# Car.net
KiCad netlist of a schematic drawn in EAGLE
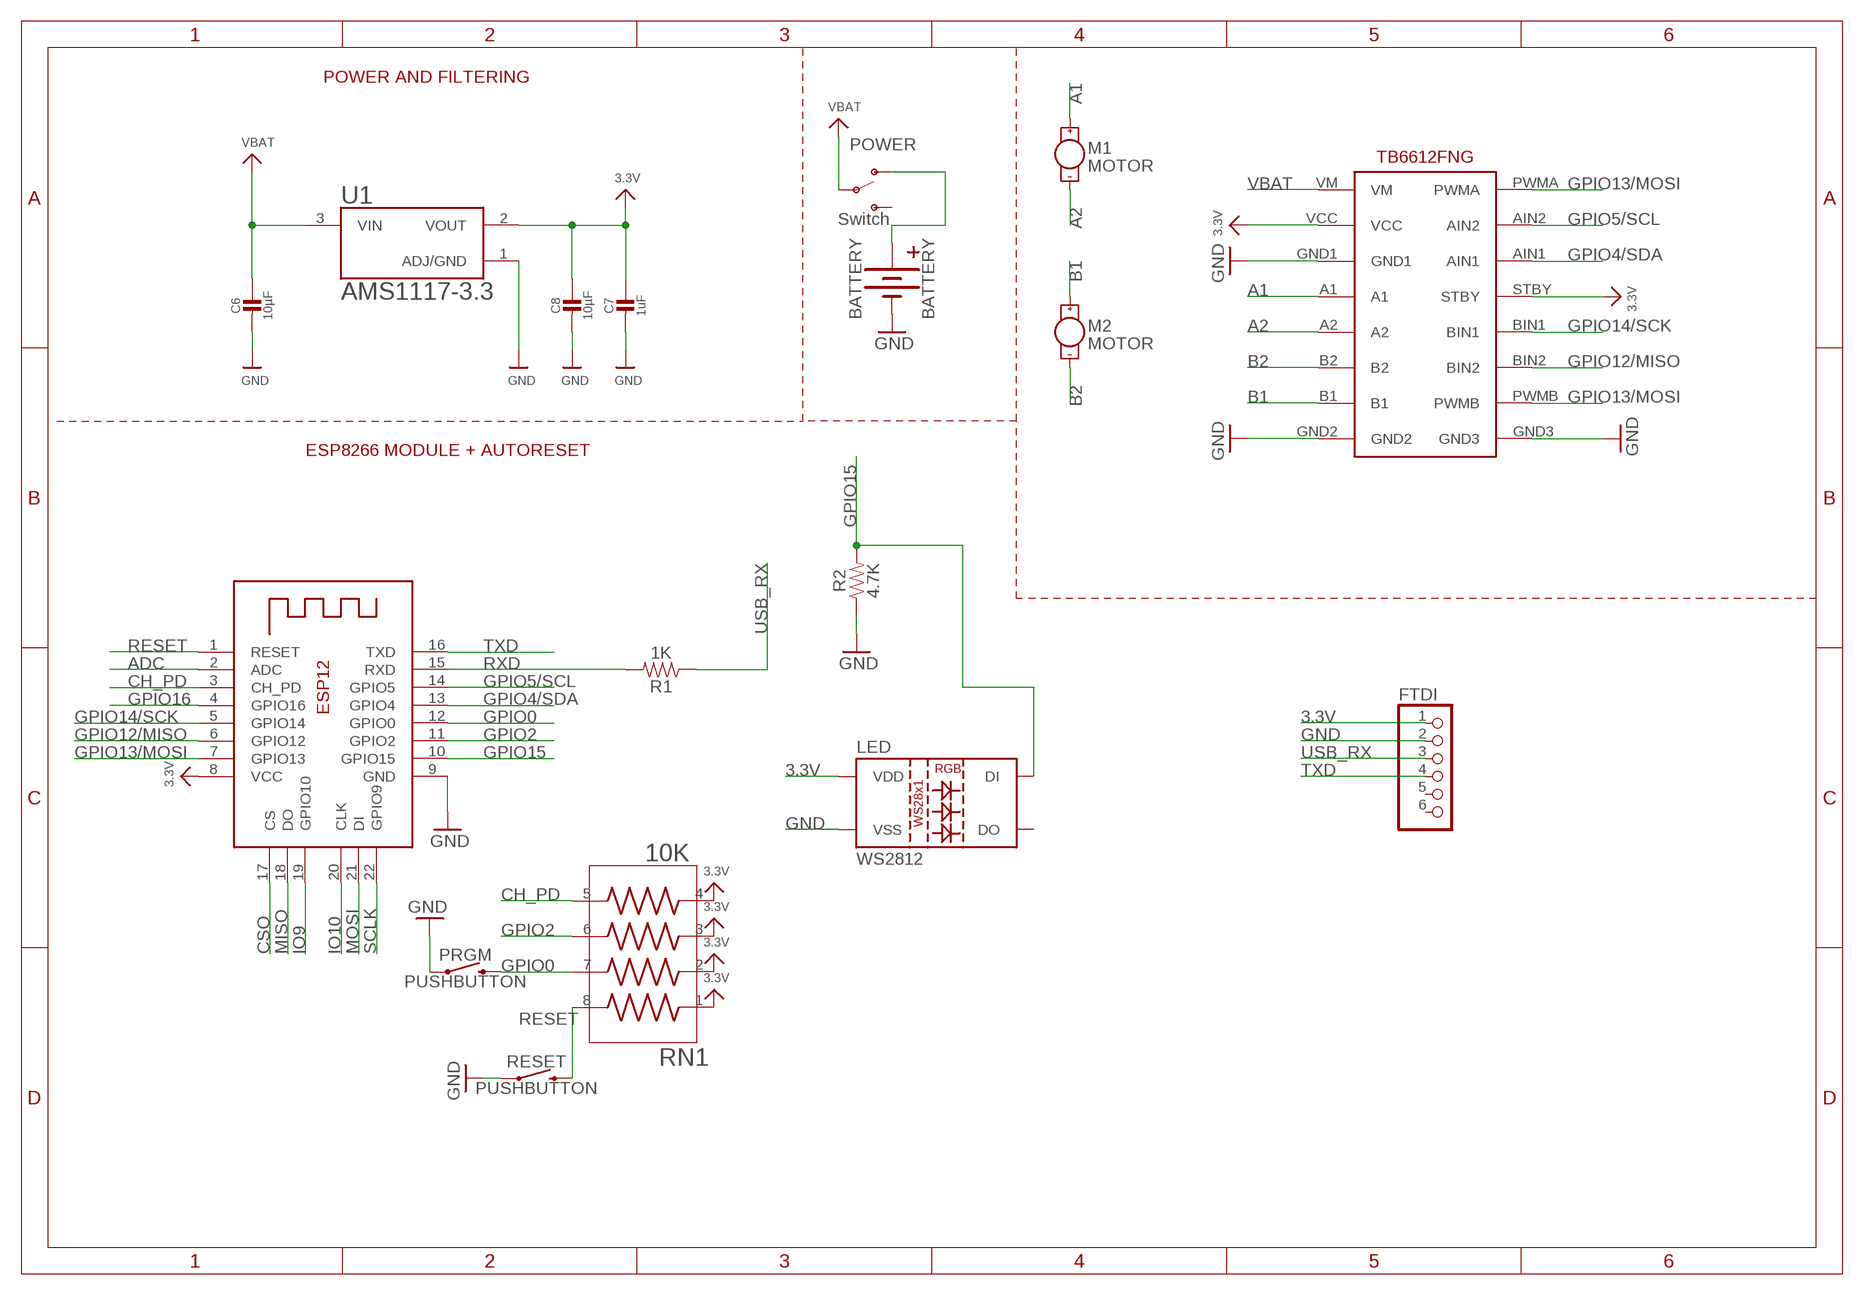
[diagram p0: schematic, sheet 1]

(export (version "E")
  (design (tool "Eeschema 10.0.6"))
  (components
    (comp (ref "BATTERY")
      (value "BATTERY")
      (footprint "eagle-import:BATTERY-AA-KIT")
      (libsource (lib "eagle-import") (part "BATTERY"))
    )
    (comp (ref "C6")
      (value "10µF")
      (footprint "eagle-import:MICROBUILDER__0805")
      (libsource (lib "eagle-import") (part "MICROBUILDER_CAP_CERAMIC_0805"))
    )
    (comp (ref "C7")
      (value "1uF")
      (footprint "eagle-import:MICROBUILDER__0603")
      (libsource (lib "eagle-import") (part "MICROBUILDER_CAP_CERAMIC_0603"))
    )
    (comp (ref "C8")
      (value "10µF")
      (footprint "eagle-import:MICROBUILDER__0805")
      (libsource (lib "eagle-import") (part "MICROBUILDER_CAP_CERAMIC_0805"))
    )
    (comp (ref "FTDI")
      (value "PINHD-1X6")
      (footprint "eagle-import:1X06")
      (libsource (lib "eagle-import") (part "PINHD-1X6"))
    )
    (comp (ref "LED")
      (value "WS2812")
      (footprint "eagle-import:LED-TRICOLOR-5050-IC")
      (libsource (lib "eagle-import") (part "WS2812"))
    )
    (comp (ref "M1")
      (value "MOTOR")
      (footprint "eagle-import:1X02_PLUS_MINUS")
      (libsource (lib "eagle-import") (part "MOTOR"))
    )
    (comp (ref "M2")
      (value "MOTOR")
      (footprint "eagle-import:1X02_PLUS_MINUS")
      (libsource (lib "eagle-import") (part "MOTOR"))
    )
    (comp (ref "POWER")
      (value "Switch")
      (footprint "eagle-import:SWITCH_SPDT_PTH_11.6X4.0MM")
      (libsource (lib "eagle-import") (part "SWITCH_SPDT_SLIDE"))
    )
    (comp (ref "PRGM")
      (value "PUSHBUTTON")
      (footprint "eagle-import:TACTILE_SWITCH_SMD_6.0X3.5MM")
      (libsource (lib "eagle-import") (part "PUSHBUTTON"))
    )
    (comp (ref "R1")
      (value "1K")
      (footprint "eagle-import:1206")
      (libsource (lib "eagle-import") (part "RESISTOR1206"))
    )
    (comp (ref "R2")
      (value "4.7K")
      (footprint "eagle-import:1206")
      (libsource (lib "eagle-import") (part "RESISTOR1206"))
    )
    (comp (ref "RESET")
      (value "PUSHBUTTON")
      (footprint "eagle-import:TACTILE_SWITCH_SMD_6.0X3.5MM")
      (libsource (lib "eagle-import") (part "PUSHBUTTON"))
    )
    (comp (ref "RN1")
      (value "10K")
      (footprint "eagle-import:RESCAF80P320X160X60-8N")
      (fields (field (name "MF") "Bourns") (field (name "MP") "CAY16-750J4LF"))
      (libsource (lib "eagle-import") (part "RESISTOR_ARRAY_1206"))
    )
    (comp (ref "TB1")
      (value "TB6612FNG")
      (footprint "eagle-import:TB6612FNG")
      (libsource (lib "eagle-import") (part "TB6612FNG"))
    )
    (comp (ref "U1")
      (value "AMS1117-3.3")
      (footprint "eagle-import:SOT229P700X180-4N")
      (fields (field (name "MF") "Advanced Monolithic Systems"))
      (libsource (lib "eagle-import") (part "AMS1117-3.3"))
    )
    (comp (ref "X2")
      (value "ESP-12")
      (footprint "eagle-import:ESP-12E")
      (libsource (lib "eagle-import") (part "ESP-12E"))
    )
  )
  (nets
    (net (code "1") (name "/A1") (class "Default")
      (node (ref "M1") (pin "+") (pinfunction "+_+") (pintype "bidirectional"))
      (node (ref "TB1") (pin "A1") (pinfunction "A1_A1") (pintype "bidirectional"))
    )
    (net (code "2") (name "/A2") (class "Default")
      (node (ref "M1") (pin "-") (pinfunction "-_-") (pintype "bidirectional"))
      (node (ref "TB1") (pin "A2") (pinfunction "A2_A2") (pintype "bidirectional"))
    )
    (net (code "3") (name "/ADC") (class "Default")
      (node (ref "X2") (pin "2") (pinfunction "ADC_2") (pintype "passive"))
    )
    (net (code "4") (name "/B1") (class "Default")
      (node (ref "M2") (pin "+") (pinfunction "+_+") (pintype "bidirectional"))
      (node (ref "TB1") (pin "B1") (pinfunction "B1_B1") (pintype "bidirectional"))
    )
    (net (code "5") (name "/B2") (class "Default")
      (node (ref "M2") (pin "-") (pinfunction "-_-") (pintype "bidirectional"))
      (node (ref "TB1") (pin "B2") (pinfunction "B2_B2") (pintype "bidirectional"))
    )
    (net (code "6") (name "/CH_PD") (class "Default")
      (node (ref "RN1") (pin "5") (pinfunction "5_5") (pintype "passive"))
      (node (ref "X2") (pin "3") (pinfunction "CH_PD_3") (pintype "input"))
    )
    (net (code "7") (name "/CSO") (class "Default")
      (node (ref "X2") (pin "17") (pinfunction "CS_17") (pintype "bidirectional"))
    )
    (net (code "8") (name "/GPIO0") (class "Default")
      (node (ref "PRGM") (pin "2") (pinfunction "2_2") (pintype "passive"))
      (node (ref "RN1") (pin "7") (pinfunction "7_7") (pintype "passive"))
      (node (ref "X2") (pin "12") (pinfunction "GPIO0_12") (pintype "bidirectional"))
    )
    (net (code "9") (name "/GPIO2") (class "Default")
      (node (ref "RN1") (pin "6") (pinfunction "6_6") (pintype "passive"))
      (node (ref "X2") (pin "11") (pinfunction "GPIO2_11") (pintype "bidirectional"))
    )
    (net (code "10") (name "/GPIO4{slash}SDA") (class "Default")
      (node (ref "TB1") (pin "AIN1") (pinfunction "AIN1_AIN1") (pintype "bidirectional"))
      (node (ref "X2") (pin "13") (pinfunction "GPIO4_13") (pintype "bidirectional"))
    )
    (net (code "11") (name "/GPIO5{slash}SCL") (class "Default")
      (node (ref "TB1") (pin "AIN2") (pinfunction "AIN2_AIN2") (pintype "bidirectional"))
      (node (ref "X2") (pin "14") (pinfunction "GPIO5_14") (pintype "bidirectional"))
    )
    (net (code "12") (name "/GPIO12{slash}MISO") (class "Default")
      (node (ref "TB1") (pin "BIN2") (pinfunction "BIN2_BIN2") (pintype "bidirectional"))
      (node (ref "X2") (pin "6") (pinfunction "GPIO12_6") (pintype "bidirectional"))
    )
    (net (code "13") (name "/GPIO13{slash}MOSI") (class "Default")
      (node (ref "TB1") (pin "PWMA") (pinfunction "PWMA_PWMA") (pintype "bidirectional"))
      (node (ref "TB1") (pin "PWMB") (pinfunction "PWMB_PWMB") (pintype "bidirectional"))
      (node (ref "X2") (pin "7") (pinfunction "GPIO13_7") (pintype "bidirectional"))
    )
    (net (code "14") (name "/GPIO14{slash}SCK") (class "Default")
      (node (ref "TB1") (pin "BIN1") (pinfunction "BIN1_BIN1") (pintype "bidirectional"))
      (node (ref "X2") (pin "5") (pinfunction "GPIO14_5") (pintype "bidirectional"))
    )
    (net (code "15") (name "/GPIO15") (class "Default")
      (node (ref "LED") (pin "DIN") (pinfunction "DI_DIN") (pintype "bidirectional"))
      (node (ref "R2") (pin "2") (pinfunction "2_2") (pintype "passive"))
      (node (ref "X2") (pin "10") (pinfunction "GPIO15_10") (pintype "bidirectional"))
    )
    (net (code "16") (name "/GPIO16") (class "Default")
      (node (ref "X2") (pin "4") (pinfunction "GPIO16_4") (pintype "bidirectional"))
    )
    (net (code "17") (name "/IO9") (class "Default")
      (node (ref "X2") (pin "19") (pinfunction "GPIO10_19") (pintype "bidirectional"))
    )
    (net (code "18") (name "/IO10") (class "Default")
      (node (ref "X2") (pin "20") (pinfunction "CLK_20") (pintype "bidirectional"))
    )
    (net (code "19") (name "/MISO") (class "Default")
      (node (ref "X2") (pin "18") (pinfunction "DO_18") (pintype "bidirectional"))
    )
    (net (code "20") (name "/MOSI") (class "Default")
      (node (ref "X2") (pin "21") (pinfunction "DI_21") (pintype "bidirectional"))
    )
    (net (code "21") (name "/RESET") (class "Default")
      (node (ref "RESET") (pin "2") (pinfunction "2_2") (pintype "passive"))
      (node (ref "RN1") (pin "8") (pinfunction "8_8") (pintype "passive"))
      (node (ref "X2") (pin "1") (pinfunction "RESET_1") (pintype "input"))
    )
    (net (code "22") (name "/RXD") (class "Default")
      (node (ref "R1") (pin "2") (pinfunction "2_2") (pintype "passive"))
      (node (ref "X2") (pin "15") (pinfunction "RXD_15") (pintype "input"))
    )
    (net (code "23") (name "/SCLK") (class "Default")
      (node (ref "X2") (pin "22") (pinfunction "GPIO9_22") (pintype "bidirectional"))
    )
    (net (code "24") (name "/TXD") (class "Default")
      (node (ref "FTDI") (pin "4") (pinfunction "4_4") (pintype "passive"))
      (node (ref "X2") (pin "16") (pinfunction "TXD_16") (pintype "output"))
    )
    (net (code "25") (name "/USB_RX") (class "Default")
      (node (ref "FTDI") (pin "3") (pinfunction "3_3") (pintype "passive"))
      (node (ref "R1") (pin "1") (pinfunction "1_1") (pintype "passive"))
    )
    (net (code "26") (name "3.3V") (class "Default")
      (node (ref "C7") (pin "1") (pinfunction "1_1") (pintype "passive"))
      (node (ref "C8") (pin "1") (pinfunction "1_1") (pintype "passive"))
      (node (ref "FTDI") (pin "1") (pinfunction "1_1") (pintype "passive"))
      (node (ref "LED") (pin "VDD") (pinfunction "VDD_VDD") (pintype "bidirectional"))
      (node (ref "RN1") (pin "1") (pinfunction "1_1") (pintype "passive"))
      (node (ref "RN1") (pin "2") (pinfunction "2_2") (pintype "passive"))
      (node (ref "RN1") (pin "3") (pinfunction "3_3") (pintype "passive"))
      (node (ref "RN1") (pin "4") (pinfunction "4_4") (pintype "passive"))
      (node (ref "TB1") (pin "STBY") (pinfunction "STBY_STBY") (pintype "bidirectional"))
      (node (ref "TB1") (pin "VCC") (pinfunction "VCC_VCC") (pintype "bidirectional"))
      (node (ref "U1") (pin "2") (pinfunction "VOUT_2") (pintype "output"))
      (node (ref "X2") (pin "8") (pinfunction "VCC_8") (pintype "power_in"))
    )
    (net (code "27") (name "GND") (class "Default")
      (node (ref "BATTERY") (pin "GND") (pinfunction "-_GND") (pintype "power_in"))
      (node (ref "C6") (pin "2") (pinfunction "2_2") (pintype "passive"))
      (node (ref "C7") (pin "2") (pinfunction "2_2") (pintype "passive"))
      (node (ref "C8") (pin "2") (pinfunction "2_2") (pintype "passive"))
      (node (ref "FTDI") (pin "2") (pinfunction "2_2") (pintype "passive"))
      (node (ref "LED") (pin "VSS") (pinfunction "VSS_VSS") (pintype "bidirectional"))
      (node (ref "PRGM") (pin "1") (pinfunction "1_1") (pintype "passive"))
      (node (ref "R2") (pin "1") (pinfunction "1_1") (pintype "passive"))
      (node (ref "RESET") (pin "1") (pinfunction "1_1") (pintype "passive"))
      (node (ref "TB1") (pin "GND1") (pinfunction "GND1_GND1") (pintype "bidirectional"))
      (node (ref "TB1") (pin "GND2") (pinfunction "GND2_GND2") (pintype "bidirectional"))
      (node (ref "TB1") (pin "GND3") (pinfunction "GND3_GND3") (pintype "bidirectional"))
      (node (ref "U1") (pin "1") (pinfunction "ADJ/GND_1") (pintype "power_in"))
      (node (ref "X2") (pin "9") (pinfunction "GND_9") (pintype "power_in"))
    )
    (net (code "28") (name "Net-(BATTERY-+)") (class "Default")
      (node (ref "BATTERY") (pin "PWR") (pinfunction "+_PWR") (pintype "power_in"))
      (node (ref "POWER") (pin "1") (pinfunction "O_1") (pintype "passive"))
    )
    (net (code "29") (name "VBAT") (class "Default")
      (node (ref "C6") (pin "1") (pinfunction "1_1") (pintype "passive"))
      (node (ref "POWER") (pin "2") (pinfunction "P_2") (pintype "passive"))
      (node (ref "TB1") (pin "VM") (pinfunction "VM_VM") (pintype "bidirectional"))
      (node (ref "U1") (pin "3") (pinfunction "VIN_3") (pintype "input"))
    )
    (net (code "30") (name "unconnected-(FTDI-Pad5)") (class "Default")
      (node (ref "FTDI") (pin "5") (pinfunction "5_5") (pintype "passive"))
    )
    (net (code "31") (name "unconnected-(FTDI-Pad6)") (class "Default")
      (node (ref "FTDI") (pin "6") (pinfunction "6_6") (pintype "passive"))
    )
    (net (code "32") (name "unconnected-(LED-DO-PadDOUT)") (class "Default")
      (node (ref "LED") (pin "DOUT") (pinfunction "DO_DOUT") (pintype "bidirectional"))
    )
    (net (code "33") (name "unconnected-(POWER-S-Pad3)") (class "Default")
      (node (ref "POWER") (pin "3") (pinfunction "S_3") (pintype "passive"))
    )
  )
)
